# SCH_PCB-Workshop_2024-10-27.net
KiCad netlist of a schematic drawn in EasyEDA
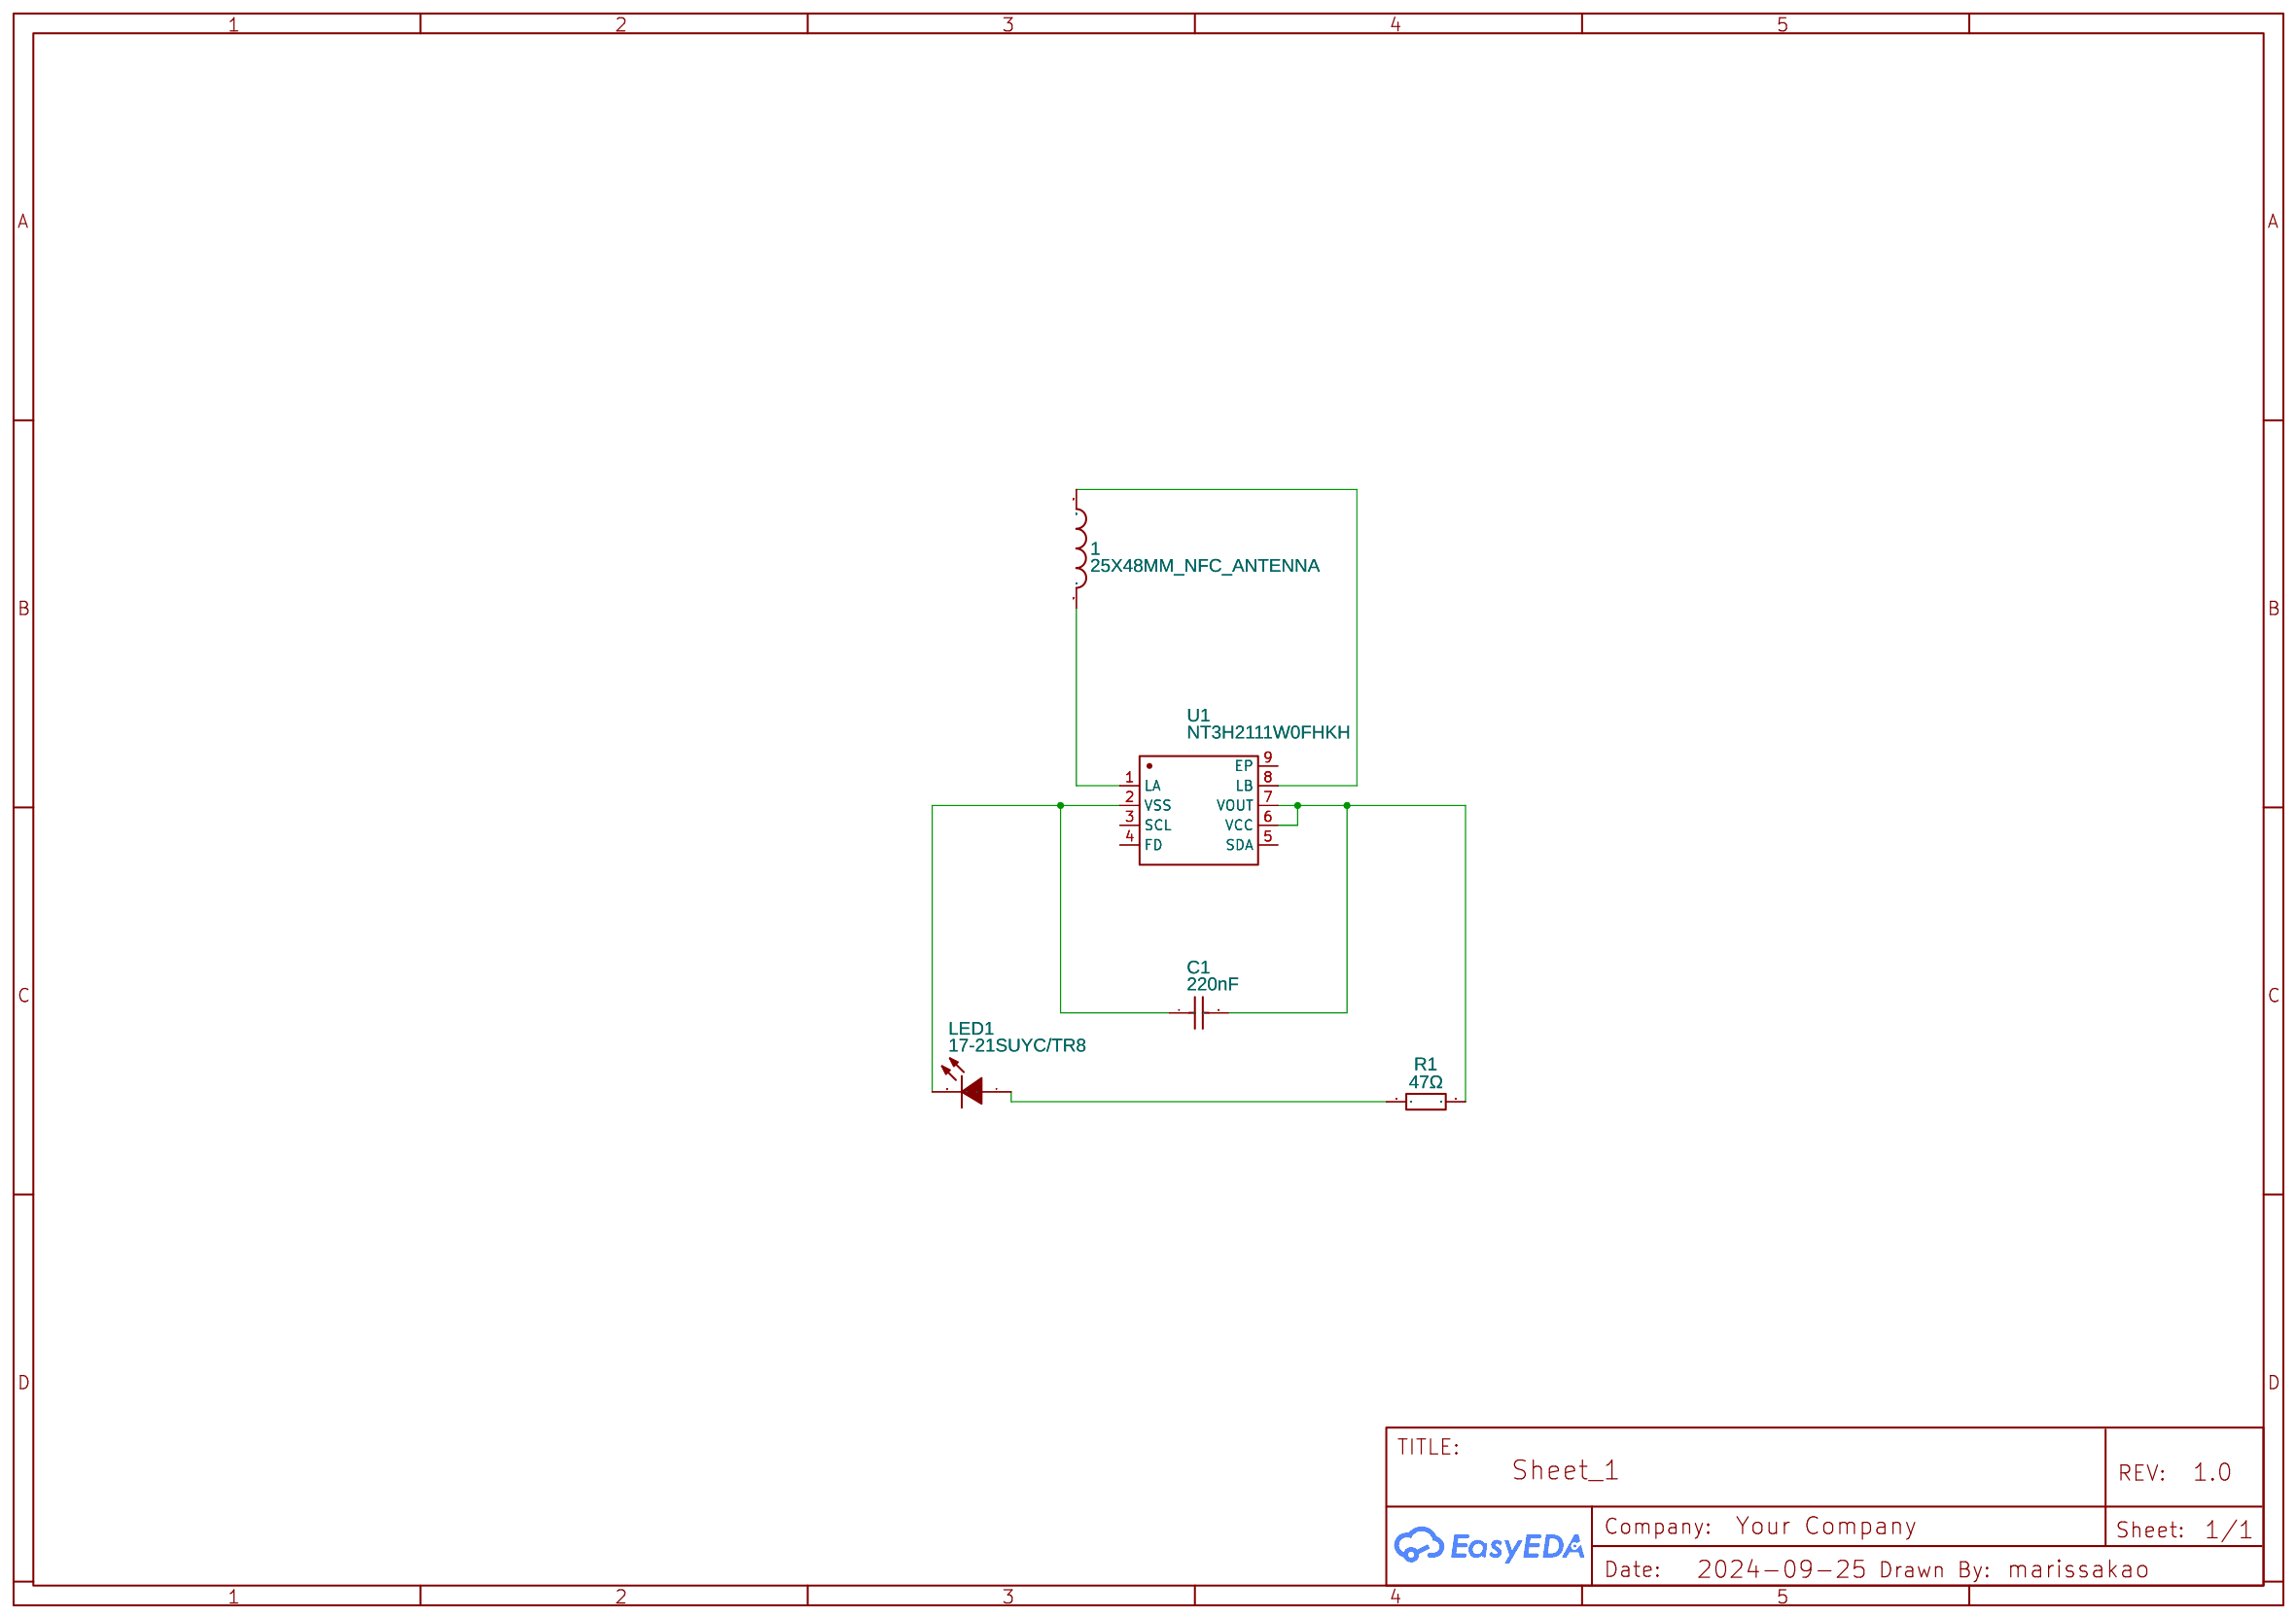
[diagram p0: schematic sheet]

(export (version "E")
  (design (tool "Eeschema 10.0.6"))
  (components
    (comp (ref "1") (value "25X48MM_NFC_ANTENNA") (libsource (lib "") (part "25X48MM_NFC_ANTENNA")))
    (comp (ref "C1")
      (value "220nF")
      (fields
        (field (name "Manufacturer Part") "CL10B224KA8NNNC")
        (field (name "Manufacturer") "SAMSUNG(三星)")
      )
      (libsource (lib "") (part "CL10B224KA8NNNC"))
    )
    (comp (ref "LED1")
      (value "17-21SUYC/TR8")
      (fields (field (name "Manufacturer Part") "KT-0805黄灯") (field (name "Manufacturer") "KENTO"))
      (libsource (lib "") (part "17-21SUYC/TR8"))
    )
    (comp (ref "R1")
      (value "47Ω")
      (fields
        (field (name "Manufacturer Part") "0603WAF470JT5E")
        (field (name "Manufacturer") "UNI-ROYAL(厚声)")
      )
      (libsource (lib "") (part "0603WAF470JT5E"))
    )
    (comp (ref "U1")
      (value "NT3H2111W0FHKH")
      (fields (field (name "Manufacturer") "NXP(恩智浦)"))
      (libsource (lib "") (part "NT3H2111W0FHKH"))
    )
  )
  (nets
    (net (code "1") (name "Net-(LED1-+)") (class "Default")
      (node (ref "LED1") (pin "1") (pinfunction "+_1") (pintype "unspecified"))
      (node (ref "R1") (pin "1") (pinfunction "1_1") (pintype "input"))
    )
    (net (code "2") (name "Net-(LED1--)") (class "Default")
      (node (ref "C1") (pin "1") (pinfunction "1_1") (pintype "input"))
      (node (ref "LED1") (pin "2") (pinfunction "-_2") (pintype "unspecified"))
      (node (ref "U1") (pin "2") (pinfunction "VSS_2") (pintype "unspecified"))
    )
    (net (code "3") (name "Net-(U1-LA)") (class "Default")
      (node (ref "1") (pin "P$2") (pinfunction "P$2_P$2") (pintype "bidirectional"))
      (node (ref "U1") (pin "1") (pinfunction "LA_1") (pintype "unspecified"))
    )
    (net (code "4") (name "Net-(U1-LB)") (class "Default")
      (node (ref "1") (pin "P$1") (pinfunction "P$1_P$1") (pintype "bidirectional"))
      (node (ref "U1") (pin "8") (pinfunction "LB_8") (pintype "unspecified"))
    )
    (net (code "5") (name "Net-(U1-VCC)") (class "Default")
      (node (ref "C1") (pin "2") (pinfunction "2_2") (pintype "input"))
      (node (ref "R1") (pin "2") (pinfunction "2_2") (pintype "input"))
      (node (ref "U1") (pin "6") (pinfunction "VCC_6") (pintype "unspecified"))
      (node (ref "U1") (pin "7") (pinfunction "VOUT_7") (pintype "unspecified"))
    )
    (net (code "6") (name "unconnected-(U1-EP-Pad9)") (class "Default")
      (node (ref "U1") (pin "9") (pinfunction "EP_9") (pintype "unspecified"))
    )
    (net (code "7") (name "unconnected-(U1-FD-Pad4)") (class "Default")
      (node (ref "U1") (pin "4") (pinfunction "FD_4") (pintype "unspecified"))
    )
    (net (code "8") (name "unconnected-(U1-SCL-Pad3)") (class "Default")
      (node (ref "U1") (pin "3") (pinfunction "SCL_3") (pintype "unspecified"))
    )
    (net (code "9") (name "unconnected-(U1-SDA-Pad5)") (class "Default")
      (node (ref "U1") (pin "5") (pinfunction "SDA_5") (pintype "unspecified"))
    )
  )
)
